# bpf.net
KiCad netlist of a schematic drawn in Altium Designer
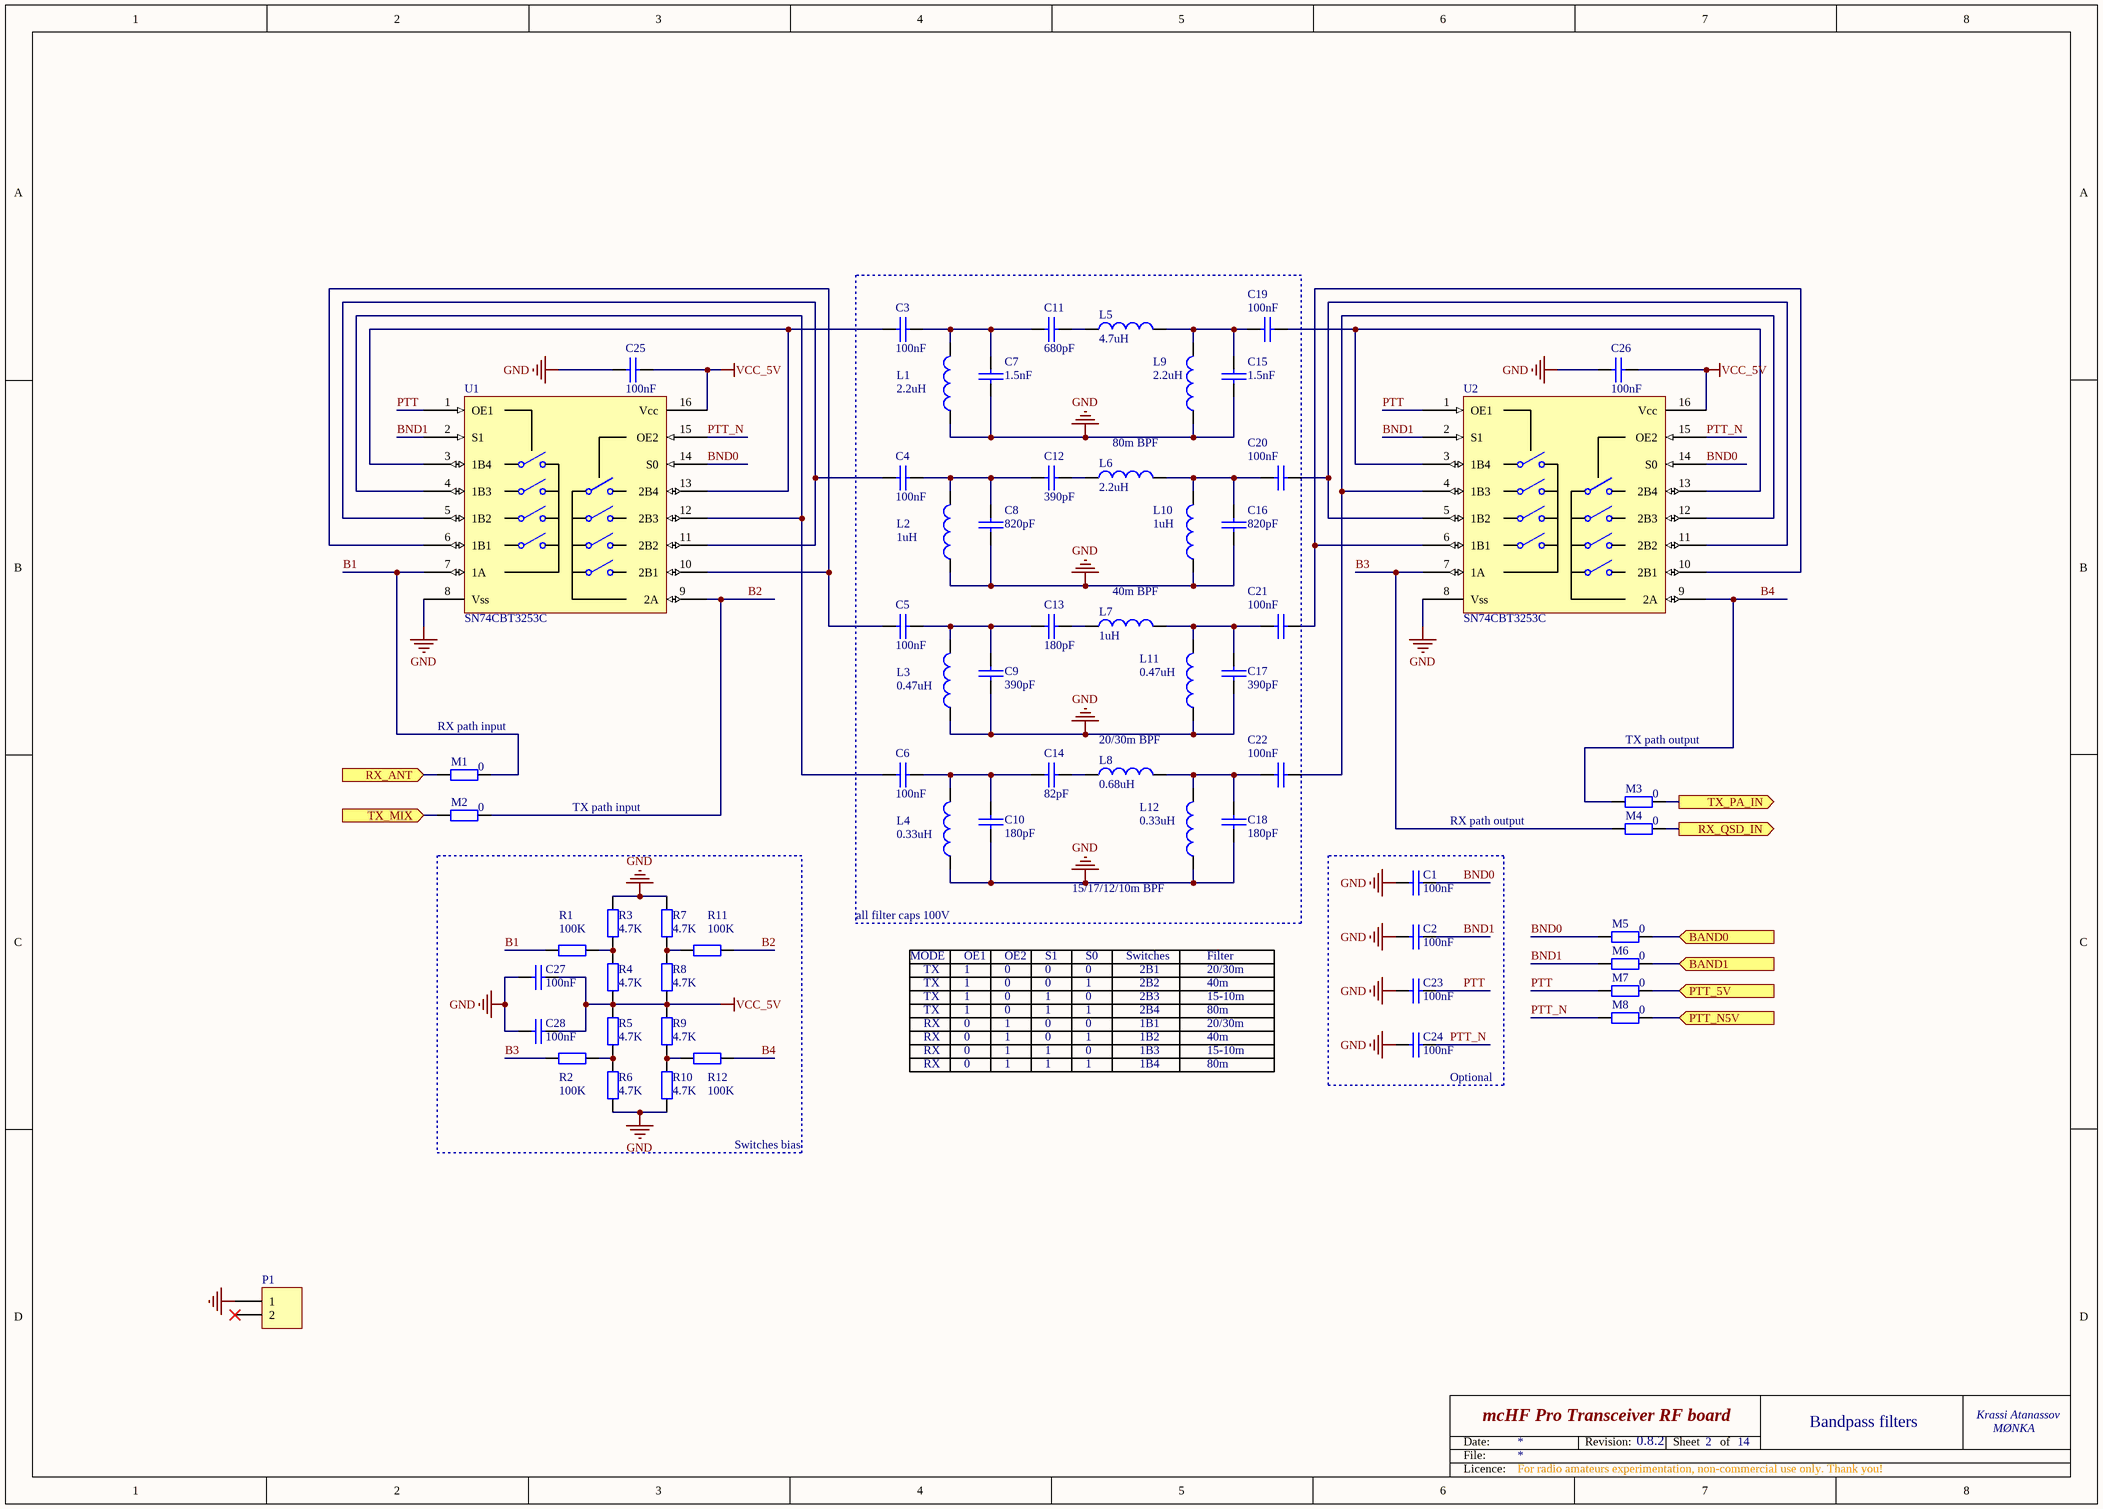
[diagram p0: bpf.SchDoc]

(export (version "E")
  (design (tool "Eeschema 10.0.6"))
  (components
    (comp (ref "C1")
      (value "100nF")
      (footprint "0805")
      (description "Capacitor")
      (libsource (lib "mcHF_rf") (part "CAP"))
    )
    (comp (ref "C2")
      (value "100nF")
      (footprint "0805")
      (description "Capacitor")
      (libsource (lib "mcHF_rf") (part "CAP"))
    )
    (comp (ref "C3")
      (value "100nF")
      (footprint "0805")
      (description "Capacitor")
      (libsource (lib "mcHF_rf") (part "CAP"))
    )
    (comp (ref "C4")
      (value "100nF")
      (footprint "0805")
      (description "Capacitor")
      (libsource (lib "mcHF_rf") (part "CAP"))
    )
    (comp (ref "C5")
      (value "100nF")
      (footprint "0805")
      (description "Capacitor")
      (libsource (lib "mcHF_rf") (part "CAP"))
    )
    (comp (ref "C6")
      (value "100nF")
      (footprint "0805")
      (description "Capacitor")
      (libsource (lib "mcHF_rf") (part "CAP"))
    )
    (comp (ref "C7")
      (value "1.5nF")
      (footprint "0805")
      (description "Capacitor")
      (libsource (lib "mcHF_rf") (part "CAP"))
    )
    (comp (ref "C8")
      (value "820pF")
      (footprint "0805")
      (description "Capacitor")
      (libsource (lib "mcHF_rf") (part "CAP"))
    )
    (comp (ref "C9")
      (value "390pF")
      (footprint "0805")
      (description "Capacitor")
      (libsource (lib "mcHF_rf") (part "CAP"))
    )
    (comp (ref "C10")
      (value "180pF")
      (footprint "0805")
      (description "Capacitor")
      (libsource (lib "mcHF_rf") (part "CAP"))
    )
    (comp (ref "C11")
      (value "680pF")
      (footprint "0805")
      (description "Capacitor")
      (libsource (lib "mcHF_rf") (part "CAP"))
    )
    (comp (ref "C12")
      (value "390pF")
      (footprint "0805")
      (description "Capacitor")
      (libsource (lib "mcHF_rf") (part "CAP"))
    )
    (comp (ref "C13")
      (value "180pF")
      (footprint "0805")
      (description "Capacitor")
      (libsource (lib "mcHF_rf") (part "CAP"))
    )
    (comp (ref "C14")
      (value "82pF")
      (footprint "0805")
      (description "Capacitor")
      (libsource (lib "mcHF_rf") (part "CAP"))
    )
    (comp (ref "C15")
      (value "1.5nF")
      (footprint "0805")
      (description "Capacitor")
      (libsource (lib "mcHF_rf") (part "CAP"))
    )
    (comp (ref "C16")
      (value "820pF")
      (footprint "0805")
      (description "Capacitor")
      (libsource (lib "mcHF_rf") (part "CAP"))
    )
    (comp (ref "C17")
      (value "390pF")
      (footprint "0805")
      (description "Capacitor")
      (libsource (lib "mcHF_rf") (part "CAP"))
    )
    (comp (ref "C18")
      (value "180pF")
      (footprint "0805")
      (description "Capacitor")
      (libsource (lib "mcHF_rf") (part "CAP"))
    )
    (comp (ref "C19")
      (value "100nF")
      (footprint "0805")
      (description "Capacitor")
      (libsource (lib "mcHF_rf") (part "CAP"))
    )
    (comp (ref "C20")
      (value "100nF")
      (footprint "0805")
      (description "Capacitor")
      (libsource (lib "mcHF_rf") (part "CAP"))
    )
    (comp (ref "C21")
      (value "100nF")
      (footprint "0805")
      (description "Capacitor")
      (libsource (lib "mcHF_rf") (part "CAP"))
    )
    (comp (ref "C22")
      (value "100nF")
      (footprint "0805")
      (description "Capacitor")
      (libsource (lib "mcHF_rf") (part "CAP"))
    )
    (comp (ref "C23")
      (value "100nF")
      (footprint "0805")
      (description "Capacitor")
      (libsource (lib "mcHF_rf") (part "CAP"))
    )
    (comp (ref "C24")
      (value "100nF")
      (footprint "0805")
      (description "Capacitor")
      (libsource (lib "mcHF_rf") (part "CAP"))
    )
    (comp (ref "C25")
      (value "100nF")
      (footprint "0805")
      (description "Capacitor")
      (libsource (lib "mcHF_rf") (part "CAP"))
    )
    (comp (ref "C26")
      (value "100nF")
      (footprint "0805")
      (description "Capacitor")
      (libsource (lib "mcHF_rf") (part "CAP"))
    )
    (comp (ref "C27")
      (value "100nF")
      (footprint "0805")
      (description "Capacitor")
      (libsource (lib "mcHF_rf") (part "CAP"))
    )
    (comp (ref "C28")
      (value "100nF")
      (footprint "0805")
      (description "Capacitor")
      (libsource (lib "mcHF_rf") (part "CAP"))
    )
    (comp (ref "L1")
      (value "2.2uH")
      (footprint "0805")
      (description "INDUCTOR SMD")
      (libsource (lib "mcHF_rf") (part "BPF_IND"))
    )
    (comp (ref "L2")
      (value "1uH")
      (footprint "0805")
      (description "INDUCTOR SMD")
      (libsource (lib "mcHF_rf") (part "BPF_IND"))
    )
    (comp (ref "L3")
      (value "0.47uH")
      (footprint "0805")
      (description "INDUCTOR SMD")
      (libsource (lib "mcHF_rf") (part "BPF_IND"))
    )
    (comp (ref "L4")
      (value "0.33uH")
      (footprint "0805")
      (description "INDUCTOR SMD")
      (libsource (lib "mcHF_rf") (part "BPF_IND"))
    )
    (comp (ref "L5")
      (value "4.7uH")
      (footprint "0805")
      (description "INDUCTOR SMD")
      (libsource (lib "mcHF_rf") (part "BPF_IND"))
    )
    (comp (ref "L6")
      (value "2.2uH")
      (footprint "0805")
      (description "INDUCTOR SMD")
      (libsource (lib "mcHF_rf") (part "BPF_IND"))
    )
    (comp (ref "L7")
      (value "1uH")
      (footprint "0805")
      (description "INDUCTOR SMD")
      (libsource (lib "mcHF_rf") (part "BPF_IND"))
    )
    (comp (ref "L8")
      (value "0.68uH")
      (footprint "0805")
      (description "INDUCTOR SMD")
      (libsource (lib "mcHF_rf") (part "BPF_IND"))
    )
    (comp (ref "L9")
      (value "2.2uH")
      (footprint "0805")
      (description "INDUCTOR SMD")
      (libsource (lib "mcHF_rf") (part "BPF_IND"))
    )
    (comp (ref "L10")
      (value "1uH")
      (footprint "0805")
      (description "INDUCTOR SMD")
      (libsource (lib "mcHF_rf") (part "BPF_IND"))
    )
    (comp (ref "L11")
      (value "0.47uH")
      (footprint "0805")
      (description "INDUCTOR SMD")
      (libsource (lib "mcHF_rf") (part "BPF_IND"))
    )
    (comp (ref "L12")
      (value "0.33uH")
      (footprint "0805")
      (description "INDUCTOR SMD")
      (libsource (lib "mcHF_rf") (part "BPF_IND"))
    )
    (comp (ref "M1")
      (value "0")
      (footprint "0805")
      (description "Resistor")
      (libsource (lib "") (part "RES_1"))
    )
    (comp (ref "M2")
      (value "0")
      (footprint "0805")
      (description "Resistor")
      (libsource (lib "") (part "RES_1"))
    )
    (comp (ref "M3")
      (value "0")
      (footprint "0805")
      (description "Resistor")
      (libsource (lib "") (part "RES_1"))
    )
    (comp (ref "M4")
      (value "0")
      (footprint "0805")
      (description "Resistor")
      (libsource (lib "") (part "RES_1"))
    )
    (comp (ref "M5")
      (value "0")
      (footprint "0805")
      (description "Resistor")
      (libsource (lib "") (part "RES_1"))
    )
    (comp (ref "M6")
      (value "0")
      (footprint "0805")
      (description "Resistor")
      (libsource (lib "") (part "RES_1"))
    )
    (comp (ref "M7")
      (value "0")
      (footprint "0805")
      (description "Resistor")
      (libsource (lib "") (part "RES_1"))
    )
    (comp (ref "M8")
      (value "0")
      (footprint "0805")
      (description "Resistor")
      (libsource (lib "") (part "RES_1"))
    )
    (comp (ref "P1")
      (value "Header 2")
      (footprint "SIP2")
      (description "Header, 2-Pin")
      (libsource (lib "__ui") (part "Header 2"))
    )
    (comp (ref "R1")
      (value "100K")
      (footprint "0805")
      (description "Resistor")
      (libsource (lib "") (part "RES_2"))
    )
    (comp (ref "R2")
      (value "100K")
      (footprint "0805")
      (description "Resistor")
      (libsource (lib "") (part "RES_2"))
    )
    (comp (ref "R3")
      (value "4.7K")
      (footprint "0805")
      (description "Resistor")
      (libsource (lib "mcHF_rf") (part "RES"))
    )
    (comp (ref "R4")
      (value "4.7K")
      (footprint "0805")
      (description "Resistor")
      (libsource (lib "mcHF_rf") (part "RES"))
    )
    (comp (ref "R5")
      (value "4.7K")
      (footprint "0805")
      (description "Resistor")
      (libsource (lib "mcHF_rf") (part "RES"))
    )
    (comp (ref "R6")
      (value "4.7K")
      (footprint "0805")
      (description "Resistor")
      (libsource (lib "mcHF_rf") (part "RES"))
    )
    (comp (ref "R7")
      (value "4.7K")
      (footprint "0805")
      (description "Resistor")
      (libsource (lib "mcHF_rf") (part "RES"))
    )
    (comp (ref "R8")
      (value "4.7K")
      (footprint "0805")
      (description "Resistor")
      (libsource (lib "mcHF_rf") (part "RES"))
    )
    (comp (ref "R9")
      (value "4.7K")
      (footprint "0805")
      (description "Resistor")
      (libsource (lib "mcHF_rf") (part "RES"))
    )
    (comp (ref "R10")
      (value "4.7K")
      (footprint "0805")
      (description "Resistor")
      (libsource (lib "mcHF_rf") (part "RES"))
    )
    (comp (ref "R11")
      (value "100K")
      (footprint "0805")
      (description "Resistor")
      (libsource (lib "") (part "RES_2"))
    )
    (comp (ref "R12")
      (value "100K")
      (footprint "0805")
      (description "Resistor")
      (libsource (lib "") (part "RES_2"))
    )
    (comp (ref "U1")
      (value "SN74CBT3253C")
      (footprint "SO-16")
      (description "Dual 4:1 Demux/Analog Switch")
      (libsource (lib "mcHF_rf") (part "SN74CBT3253C"))
    )
    (comp (ref "U2")
      (value "SN74CBT3253C")
      (footprint "SO-16")
      (description "Dual 4:1 Demux/Analog Switch")
      (libsource (lib "mcHF_rf") (part "SN74CBT3253C"))
    )
  )
  (nets
    (net (code "1") (name "/B1") (class "Default")
      (node (ref "M1") (pin "1") (pinfunction "1_1") (pintype "passive"))
      (node (ref "R1") (pin "1") (pinfunction "1_1") (pintype "passive"))
      (node (ref "U1") (pin "7") (pinfunction "1A_7") (pintype "bidirectional"))
    )
    (net (code "2") (name "/B2") (class "Default")
      (node (ref "M2") (pin "1") (pinfunction "1_1") (pintype "passive"))
      (node (ref "R11") (pin "2") (pinfunction "2_2") (pintype "passive"))
      (node (ref "U1") (pin "9") (pinfunction "2A_9") (pintype "bidirectional"))
    )
    (net (code "3") (name "/B3") (class "Default")
      (node (ref "M4") (pin "2") (pinfunction "2_2") (pintype "passive"))
      (node (ref "R2") (pin "1") (pinfunction "1_1") (pintype "passive"))
      (node (ref "U2") (pin "7") (pinfunction "1A_7") (pintype "bidirectional"))
    )
    (net (code "4") (name "/B4") (class "Default")
      (node (ref "M3") (pin "2") (pinfunction "2_2") (pintype "passive"))
      (node (ref "R12") (pin "2") (pinfunction "2_2") (pintype "passive"))
      (node (ref "U2") (pin "9") (pinfunction "2A_9") (pintype "bidirectional"))
    )
    (net (code "5") (name "/BAND0") (class "Default")
      (node (ref "M5") (pin "1") (pinfunction "1_1") (pintype "passive"))
    )
    (net (code "6") (name "/BAND1") (class "Default")
      (node (ref "M6") (pin "1") (pinfunction "1_1") (pintype "passive"))
    )
    (net (code "7") (name "/BND0") (class "Default")
      (node (ref "C1") (pin "1") (pinfunction "1_1") (pintype "passive"))
      (node (ref "M5") (pin "2") (pinfunction "2_2") (pintype "passive"))
      (node (ref "U1") (pin "14") (pinfunction "S0_14") (pintype "input"))
      (node (ref "U2") (pin "14") (pinfunction "S0_14") (pintype "input"))
    )
    (net (code "8") (name "/BND1") (class "Default")
      (node (ref "C2") (pin "1") (pinfunction "1_1") (pintype "passive"))
      (node (ref "M6") (pin "2") (pinfunction "2_2") (pintype "passive"))
      (node (ref "U1") (pin "2") (pinfunction "S1_2") (pintype "input"))
      (node (ref "U2") (pin "2") (pinfunction "S1_2") (pintype "input"))
    )
    (net (code "9") (name "/PTT") (class "Default")
      (node (ref "C23") (pin "1") (pinfunction "1_1") (pintype "passive"))
      (node (ref "M7") (pin "2") (pinfunction "2_2") (pintype "passive"))
      (node (ref "U1") (pin "1") (pinfunction "OE1_1") (pintype "input"))
      (node (ref "U2") (pin "1") (pinfunction "OE1_1") (pintype "input"))
    )
    (net (code "10") (name "/PTT_5V") (class "Default")
      (node (ref "M7") (pin "1") (pinfunction "1_1") (pintype "passive"))
    )
    (net (code "11") (name "/PTT_N") (class "Default")
      (node (ref "C24") (pin "1") (pinfunction "1_1") (pintype "passive"))
      (node (ref "M8") (pin "2") (pinfunction "2_2") (pintype "passive"))
      (node (ref "U1") (pin "15") (pinfunction "OE2_15") (pintype "input"))
      (node (ref "U2") (pin "15") (pinfunction "OE2_15") (pintype "input"))
    )
    (net (code "12") (name "/PTT_N5V") (class "Default")
      (node (ref "M8") (pin "1") (pinfunction "1_1") (pintype "passive"))
    )
    (net (code "13") (name "/RX_ANT") (class "Default")
      (node (ref "M1") (pin "2") (pinfunction "2_2") (pintype "passive"))
    )
    (net (code "14") (name "/RX_QSD_IN") (class "Default")
      (node (ref "M4") (pin "1") (pinfunction "1_1") (pintype "passive"))
    )
    (net (code "15") (name "/TX_MIX") (class "Default")
      (node (ref "M2") (pin "2") (pinfunction "2_2") (pintype "passive"))
    )
    (net (code "16") (name "/TX_PA_IN") (class "Default")
      (node (ref "M3") (pin "1") (pinfunction "1_1") (pintype "passive"))
    )
    (net (code "17") (name "GND") (class "Default")
      (node (ref "C1") (pin "2") (pinfunction "2_2") (pintype "passive"))
      (node (ref "C10") (pin "1") (pinfunction "1_1") (pintype "passive"))
      (node (ref "C15") (pin "2") (pinfunction "2_2") (pintype "passive"))
      (node (ref "C16") (pin "2") (pinfunction "2_2") (pintype "passive"))
      (node (ref "C17") (pin "1") (pinfunction "1_1") (pintype "passive"))
      (node (ref "C18") (pin "1") (pinfunction "1_1") (pintype "passive"))
      (node (ref "C2") (pin "2") (pinfunction "2_2") (pintype "passive"))
      (node (ref "C23") (pin "2") (pinfunction "2_2") (pintype "passive"))
      (node (ref "C24") (pin "2") (pinfunction "2_2") (pintype "passive"))
      (node (ref "C25") (pin "2") (pinfunction "2_2") (pintype "passive"))
      (node (ref "C26") (pin "2") (pinfunction "2_2") (pintype "passive"))
      (node (ref "C27") (pin "2") (pinfunction "2_2") (pintype "passive"))
      (node (ref "C28") (pin "2") (pinfunction "2_2") (pintype "passive"))
      (node (ref "C7") (pin "2") (pinfunction "2_2") (pintype "passive"))
      (node (ref "C8") (pin "2") (pinfunction "2_2") (pintype "passive"))
      (node (ref "C9") (pin "1") (pinfunction "1_1") (pintype "passive"))
      (node (ref "L1") (pin "1") (pinfunction "1_1") (pintype "passive"))
      (node (ref "L10") (pin "1") (pinfunction "1_1") (pintype "passive"))
      (node (ref "L11") (pin "1") (pinfunction "1_1") (pintype "passive"))
      (node (ref "L12") (pin "1") (pinfunction "1_1") (pintype "passive"))
      (node (ref "L2") (pin "1") (pinfunction "1_1") (pintype "passive"))
      (node (ref "L3") (pin "1") (pinfunction "1_1") (pintype "passive"))
      (node (ref "L4") (pin "1") (pinfunction "1_1") (pintype "passive"))
      (node (ref "L9") (pin "1") (pinfunction "1_1") (pintype "passive"))
      (node (ref "P1") (pin "1") (pinfunction "1_1") (pintype "passive"))
      (node (ref "R10") (pin "2") (pinfunction "2_2") (pintype "passive"))
      (node (ref "R3") (pin "1") (pinfunction "1_1") (pintype "passive"))
      (node (ref "R6") (pin "2") (pinfunction "2_2") (pintype "passive"))
      (node (ref "R7") (pin "1") (pinfunction "1_1") (pintype "passive"))
      (node (ref "U1") (pin "8") (pinfunction "Vss_8") (pintype "power_in"))
      (node (ref "U2") (pin "8") (pinfunction "Vss_8") (pintype "power_in"))
    )
    (net (code "18") (name "Net-(C10-Pad2)") (class "Default")
      (node (ref "C10") (pin "2") (pinfunction "2_2") (pintype "passive"))
      (node (ref "C14") (pin "1") (pinfunction "1_1") (pintype "passive"))
      (node (ref "C6") (pin "1") (pinfunction "1_1") (pintype "passive"))
      (node (ref "L4") (pin "2") (pinfunction "2_2") (pintype "passive"))
    )
    (net (code "19") (name "Net-(C11-Pad1)") (class "Default")
      (node (ref "C11") (pin "1") (pinfunction "1_1") (pintype "passive"))
      (node (ref "C3") (pin "1") (pinfunction "1_1") (pintype "passive"))
      (node (ref "C7") (pin "1") (pinfunction "1_1") (pintype "passive"))
      (node (ref "L1") (pin "2") (pinfunction "2_2") (pintype "passive"))
    )
    (net (code "20") (name "Net-(C11-Pad2)") (class "Default")
      (node (ref "C11") (pin "2") (pinfunction "2_2") (pintype "passive"))
      (node (ref "L5") (pin "1") (pinfunction "1_1") (pintype "passive"))
    )
    (net (code "21") (name "Net-(C12-Pad1)") (class "Default")
      (node (ref "C12") (pin "1") (pinfunction "1_1") (pintype "passive"))
      (node (ref "C4") (pin "1") (pinfunction "1_1") (pintype "passive"))
      (node (ref "C8") (pin "1") (pinfunction "1_1") (pintype "passive"))
      (node (ref "L2") (pin "2") (pinfunction "2_2") (pintype "passive"))
    )
    (net (code "22") (name "Net-(C12-Pad2)") (class "Default")
      (node (ref "C12") (pin "2") (pinfunction "2_2") (pintype "passive"))
      (node (ref "L6") (pin "1") (pinfunction "1_1") (pintype "passive"))
    )
    (net (code "23") (name "Net-(C13-Pad1)") (class "Default")
      (node (ref "C13") (pin "1") (pinfunction "1_1") (pintype "passive"))
      (node (ref "C5") (pin "1") (pinfunction "1_1") (pintype "passive"))
      (node (ref "C9") (pin "2") (pinfunction "2_2") (pintype "passive"))
      (node (ref "L3") (pin "2") (pinfunction "2_2") (pintype "passive"))
    )
    (net (code "24") (name "Net-(C13-Pad2)") (class "Default")
      (node (ref "C13") (pin "2") (pinfunction "2_2") (pintype "passive"))
      (node (ref "L7") (pin "1") (pinfunction "1_1") (pintype "passive"))
    )
    (net (code "25") (name "Net-(C14-Pad2)") (class "Default")
      (node (ref "C14") (pin "2") (pinfunction "2_2") (pintype "passive"))
      (node (ref "L8") (pin "1") (pinfunction "1_1") (pintype "passive"))
    )
    (net (code "26") (name "Net-(C15-Pad1)") (class "Default")
      (node (ref "C15") (pin "1") (pinfunction "1_1") (pintype "passive"))
      (node (ref "C19") (pin "2") (pinfunction "2_2") (pintype "passive"))
      (node (ref "L5") (pin "2") (pinfunction "2_2") (pintype "passive"))
      (node (ref "L9") (pin "2") (pinfunction "2_2") (pintype "passive"))
    )
    (net (code "27") (name "Net-(C16-Pad1)") (class "Default")
      (node (ref "C16") (pin "1") (pinfunction "1_1") (pintype "passive"))
      (node (ref "C20") (pin "2") (pinfunction "2_2") (pintype "passive"))
      (node (ref "L10") (pin "2") (pinfunction "2_2") (pintype "passive"))
      (node (ref "L6") (pin "2") (pinfunction "2_2") (pintype "passive"))
    )
    (net (code "28") (name "Net-(C17-Pad2)") (class "Default")
      (node (ref "C17") (pin "2") (pinfunction "2_2") (pintype "passive"))
      (node (ref "C21") (pin "2") (pinfunction "2_2") (pintype "passive"))
      (node (ref "L11") (pin "2") (pinfunction "2_2") (pintype "passive"))
      (node (ref "L7") (pin "2") (pinfunction "2_2") (pintype "passive"))
    )
    (net (code "29") (name "Net-(C18-Pad2)") (class "Default")
      (node (ref "C18") (pin "2") (pinfunction "2_2") (pintype "passive"))
      (node (ref "C22") (pin "2") (pinfunction "2_2") (pintype "passive"))
      (node (ref "L12") (pin "2") (pinfunction "2_2") (pintype "passive"))
      (node (ref "L8") (pin "2") (pinfunction "2_2") (pintype "passive"))
    )
    (net (code "30") (name "Net-(R1-Pad2)") (class "Default")
      (node (ref "R1") (pin "2") (pinfunction "2_2") (pintype "passive"))
      (node (ref "R3") (pin "2") (pinfunction "2_2") (pintype "passive"))
      (node (ref "R4") (pin "1") (pinfunction "1_1") (pintype "passive"))
    )
    (net (code "31") (name "Net-(R2-Pad2)") (class "Default")
      (node (ref "R2") (pin "2") (pinfunction "2_2") (pintype "passive"))
      (node (ref "R5") (pin "2") (pinfunction "2_2") (pintype "passive"))
      (node (ref "R6") (pin "1") (pinfunction "1_1") (pintype "passive"))
    )
    (net (code "32") (name "Net-(R10-Pad1)") (class "Default")
      (node (ref "R10") (pin "1") (pinfunction "1_1") (pintype "passive"))
      (node (ref "R12") (pin "1") (pinfunction "1_1") (pintype "passive"))
      (node (ref "R9") (pin "2") (pinfunction "2_2") (pintype "passive"))
    )
    (net (code "33") (name "Net-(R11-Pad1)") (class "Default")
      (node (ref "R11") (pin "1") (pinfunction "1_1") (pintype "passive"))
      (node (ref "R7") (pin "2") (pinfunction "2_2") (pintype "passive"))
      (node (ref "R8") (pin "1") (pinfunction "1_1") (pintype "passive"))
    )
    (net (code "34") (name "Net-(U1-1B1)") (class "Default")
      (node (ref "C5") (pin "2") (pinfunction "2_2") (pintype "passive"))
      (node (ref "U1") (pin "10") (pinfunction "2B1_10") (pintype "bidirectional"))
      (node (ref "U1") (pin "6") (pinfunction "1B1_6") (pintype "bidirectional"))
    )
    (net (code "35") (name "Net-(U1-1B2)") (class "Default")
      (node (ref "C4") (pin "2") (pinfunction "2_2") (pintype "passive"))
      (node (ref "U1") (pin "11") (pinfunction "2B2_11") (pintype "bidirectional"))
      (node (ref "U1") (pin "5") (pinfunction "1B2_5") (pintype "bidirectional"))
    )
    (net (code "36") (name "Net-(U1-1B3)") (class "Default")
      (node (ref "C6") (pin "2") (pinfunction "2_2") (pintype "passive"))
      (node (ref "U1") (pin "12") (pinfunction "2B3_12") (pintype "bidirectional"))
      (node (ref "U1") (pin "4") (pinfunction "1B3_4") (pintype "bidirectional"))
    )
    (net (code "37") (name "Net-(U1-1B4)") (class "Default")
      (node (ref "C3") (pin "2") (pinfunction "2_2") (pintype "passive"))
      (node (ref "U1") (pin "13") (pinfunction "2B4_13") (pintype "bidirectional"))
      (node (ref "U1") (pin "3") (pinfunction "1B4_3") (pintype "bidirectional"))
    )
    (net (code "38") (name "Net-(U2-1B1)") (class "Default")
      (node (ref "C21") (pin "1") (pinfunction "1_1") (pintype "passive"))
      (node (ref "U2") (pin "10") (pinfunction "2B1_10") (pintype "bidirectional"))
      (node (ref "U2") (pin "6") (pinfunction "1B1_6") (pintype "bidirectional"))
    )
    (net (code "39") (name "Net-(U2-1B2)") (class "Default")
      (node (ref "C20") (pin "1") (pinfunction "1_1") (pintype "passive"))
      (node (ref "U2") (pin "11") (pinfunction "2B2_11") (pintype "bidirectional"))
      (node (ref "U2") (pin "5") (pinfunction "1B2_5") (pintype "bidirectional"))
    )
    (net (code "40") (name "Net-(U2-1B3)") (class "Default")
      (node (ref "C22") (pin "1") (pinfunction "1_1") (pintype "passive"))
      (node (ref "U2") (pin "12") (pinfunction "2B3_12") (pintype "bidirectional"))
      (node (ref "U2") (pin "4") (pinfunction "1B3_4") (pintype "bidirectional"))
    )
    (net (code "41") (name "Net-(U2-1B4)") (class "Default")
      (node (ref "C19") (pin "1") (pinfunction "1_1") (pintype "passive"))
      (node (ref "U2") (pin "13") (pinfunction "2B4_13") (pintype "bidirectional"))
      (node (ref "U2") (pin "3") (pinfunction "1B4_3") (pintype "bidirectional"))
    )
    (net (code "42") (name "VCC_5V") (class "Default")
      (node (ref "C25") (pin "1") (pinfunction "1_1") (pintype "passive"))
      (node (ref "C26") (pin "1") (pinfunction "1_1") (pintype "passive"))
      (node (ref "C27") (pin "1") (pinfunction "1_1") (pintype "passive"))
      (node (ref "C28") (pin "1") (pinfunction "1_1") (pintype "passive"))
      (node (ref "R4") (pin "2") (pinfunction "2_2") (pintype "passive"))
      (node (ref "R5") (pin "1") (pinfunction "1_1") (pintype "passive"))
      (node (ref "R8") (pin "2") (pinfunction "2_2") (pintype "passive"))
      (node (ref "R9") (pin "1") (pinfunction "1_1") (pintype "passive"))
      (node (ref "U1") (pin "16") (pinfunction "Vcc_16") (pintype "power_in"))
      (node (ref "U2") (pin "16") (pinfunction "Vcc_16") (pintype "power_in"))
    )
    (net (code "43") (name "unconnected-(P1-Pad2)") (class "Default")
      (node (ref "P1") (pin "2") (pinfunction "2_2") (pintype "passive+no_connect"))
    )
  )
)
